# Schematic1.net
KiCad netlist of a schematic drawn in Altium Designer
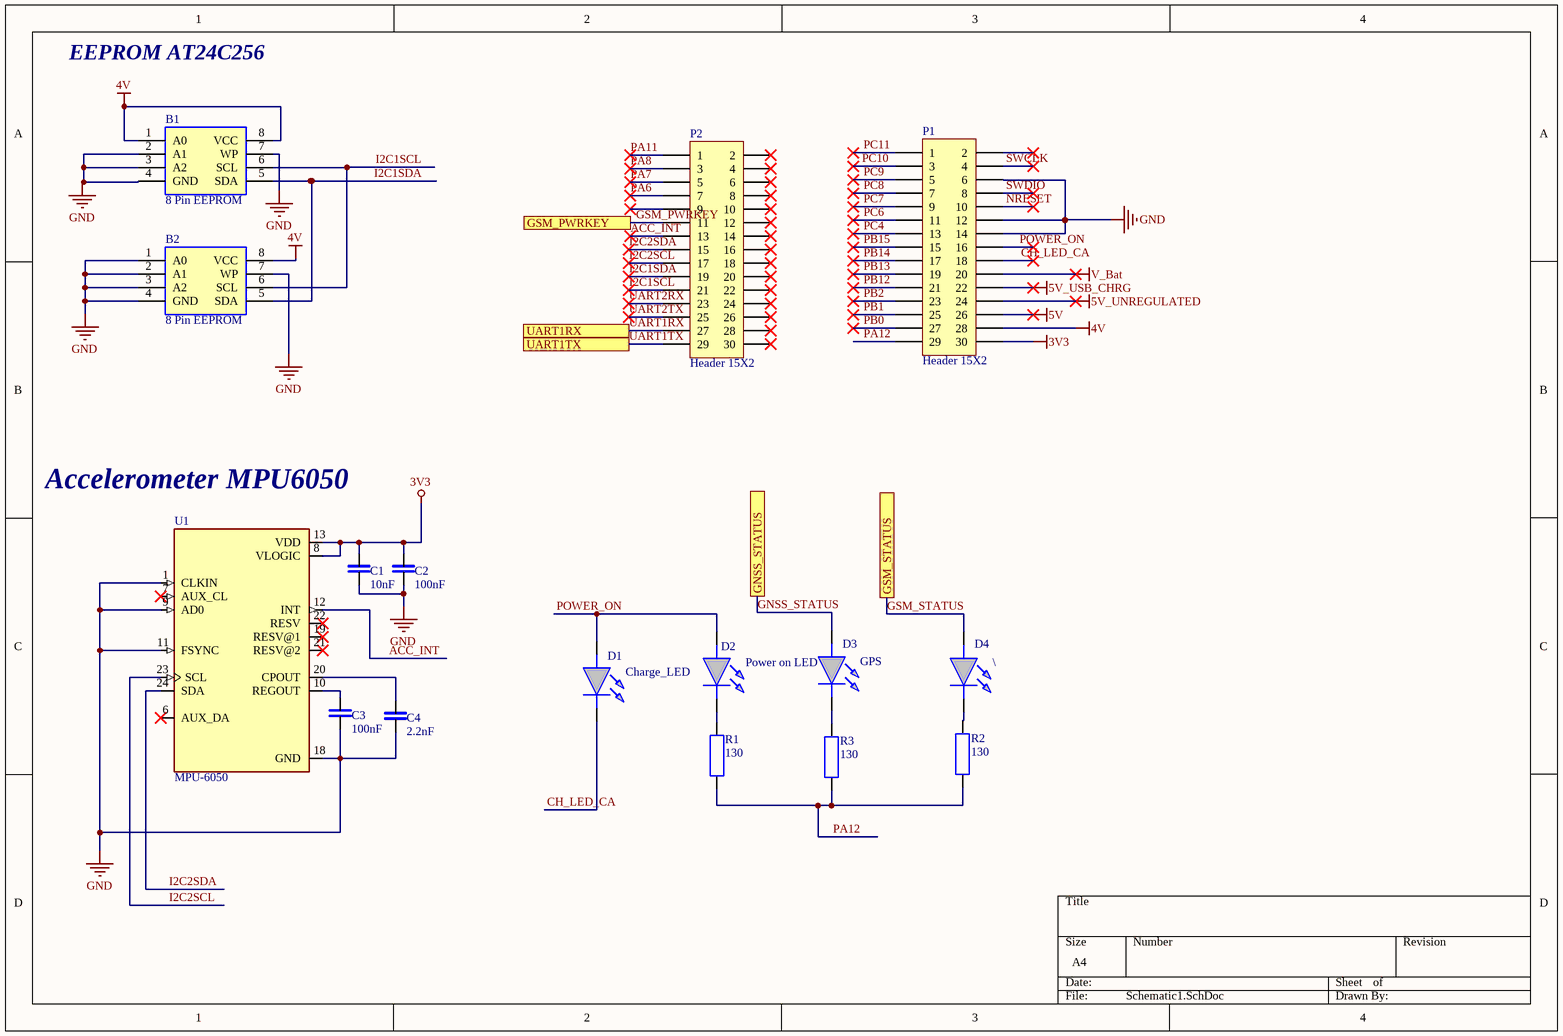
[diagram p0: Schematic1.SchDoc]

(export (version "E")
  (design (tool "Eeschema 10.0.6"))
  (components
    (comp (ref "B1")
      (value "8 Pin EEPROM")
      (footprint "AT24C256")
      (fields
        (field (name "MANUFACTURER_PART_NUMBER") "AT24C256C-SSHL-T")
        (field (name "MOUSER PART NUMBER") "556-AT24C256C-SSHL-T")
      )
      (libsource (lib "IC") (part "AT24C256C"))
    )
    (comp (ref "B2")
      (value "8 Pin EEPROM")
      (footprint "AT24C256")
      (fields
        (field (name "MANUFACTURER_PART_NUMBER") "AT24C256C-SSHL-T")
        (field (name "MOUSER PART NUMBER") "556-AT24C256C-SSHL-T")
      )
      (libsource (lib "IC") (part "AT24C256C"))
    )
    (comp (ref "C1")
      (value "10nF")
      (footprint "CAP_0805")
      (fields (field (name "MP") "LD051A270KAB2A"))
      (libsource (lib "Passive_Components") (part "SMT_CAP"))
    )
    (comp (ref "C2")
      (value "100nF")
      (footprint "CAP_0805")
      (fields (field (name "MP") "LD051A270KAB2A"))
      (libsource (lib "Passive_Components") (part "SMT_CAP"))
    )
    (comp (ref "C3")
      (value "100nF")
      (footprint "CAP_0805")
      (fields (field (name "MP") "LD051A270KAB2A"))
      (libsource (lib "Passive_Components") (part "SMT_CAP"))
    )
    (comp (ref "C4")
      (value "2.2nF")
      (footprint "CAP_0805")
      (fields (field (name "MP") "LD051A270KAB2A"))
      (libsource (lib "Passive_Components") (part "SMT_CAP"))
    )
    (comp (ref "D1")
      (value "Charge_LED")
      (footprint "LED_0805")
      (fields
        (field (name "MANUFACTURER_PART_NUMBER") "HSMH-C170")
        (field (name "MOUSER PART NUMBER") "630-HSMH-C170")
      )
      (libsource (lib "Diodes") (part "LED"))
    )
    (comp (ref "D2")
      (value "Power on LED")
      (footprint "LED_0805")
      (fields
        (field (name "MANUFACTURER_PART_NUMBER") "HSMH-C170")
        (field (name "MOUSER PART NUMBER") "630-HSMH-C170")
      )
      (libsource (lib "Diodes") (part "LED"))
    )
    (comp (ref "D3")
      (value "GPS")
      (footprint "LED_0805")
      (fields
        (field (name "MANUFACTURER_PART_NUMBER") "HSMH-C170")
        (field (name "MOUSER PART NUMBER") "630-HSMH-C170")
      )
      (libsource (lib "Diodes") (part "LED"))
    )
    (comp (ref "D4")
      (value "\\")
      (footprint "LED_0805")
      (fields
        (field (name "MANUFACTURER_PART_NUMBER") "HSMH-C170")
        (field (name "MOUSER PART NUMBER") "630-HSMH-C170")
      )
      (libsource (lib "Diodes") (part "LED"))
    )
    (comp (ref "P1")
      (value "Header 15X2")
      (footprint "HDR2X15")
      (description "Header, 15-Pin, Dual row")
      (fields (field (name "PUBLISHER") "Altium Limited"))
      (libsource (lib "Miscellaneous Connectors") (part "Header 15X2"))
    )
    (comp (ref "P2")
      (value "Header 15X2")
      (footprint "HDR2X15")
      (description "Header, 15-Pin, Dual row")
      (fields (field (name "PUBLISHER") "Altium Limited"))
      (libsource (lib "Miscellaneous Connectors") (part "Header 15X2"))
    )
    (comp (ref "R1")
      (value "130")
      (footprint "RES_0805")
      (fields
        (field (name "MP") "2-2176053-0")
        (field (name "TOLERANCE") "1%")
        (field (name "MF") "TE Connectivity")
      )
      (libsource (lib "Passive_Components") (part "SMT_RES"))
    )
    (comp (ref "R2")
      (value "130")
      (footprint "RES_0805")
      (fields
        (field (name "MP") "2-2176053-0")
        (field (name "TOLERANCE") "1%")
        (field (name "MF") "TE Connectivity")
      )
      (libsource (lib "Passive_Components") (part "SMT_RES"))
    )
    (comp (ref "R3")
      (value "130")
      (footprint "RES_0805")
      (fields
        (field (name "MP") "2-2176053-0")
        (field (name "TOLERANCE") "1%")
        (field (name "MF") "TE Connectivity")
      )
      (libsource (lib "Passive_Components") (part "SMT_RES"))
    )
    (comp (ref "U1")
      (value "MPU-6050")
      (footprint "MPU_6050")
      (fields (field (name "MF") "TDK InvenSense"))
      (libsource (lib "IC") (part "MPU-6050"))
    )
  )
  (nets
    (net (code "2") (name "/ACC_INT") (class "Default")
      (node (ref "P2") (pin "13") (pinfunction "13_13") (pintype "passive"))
      (node (ref "U1") (pin "12") (pinfunction "INT_12") (pintype "output"))
    )
    (net (code "3") (name "/CH_LED_CA") (class "Default")
      (node (ref "D1") (pin "1") (pinfunction "K_1") (pintype "passive"))
      (node (ref "P1") (pin "18") (pinfunction "18_18") (pintype "passive"))
    )
    (net (code "4") (name "/GNSS_STATUS") (class "Default")
      (node (ref "D3") (pin "2") (pinfunction "A_2") (pintype "passive"))
    )
    (net (code "5") (name "/GSM_PWRKEY") (class "Default")
      (node (ref "P2") (pin "11") (pinfunction "11_11") (pintype "passive"))
    )
    (net (code "6") (name "/GSM_STATUS") (class "Default")
      (node (ref "D4") (pin "2") (pinfunction "A_2") (pintype "passive"))
    )
    (net (code "7") (name "/I2C1SCL") (class "Default")
      (node (ref "B1") (pin "6") (pinfunction "SCL_6") (pintype "passive"))
      (node (ref "B2") (pin "6") (pinfunction "SCL_6") (pintype "passive"))
      (node (ref "P2") (pin "21") (pinfunction "21_21") (pintype "passive"))
    )
    (net (code "8") (name "/I2C1SDA") (class "Default")
      (node (ref "B1") (pin "5") (pinfunction "SDA_5") (pintype "passive"))
      (node (ref "B2") (pin "5") (pinfunction "SDA_5") (pintype "passive"))
      (node (ref "P2") (pin "19") (pinfunction "19_19") (pintype "passive"))
    )
    (net (code "9") (name "/I2C2SCL") (class "Default")
      (node (ref "P2") (pin "17") (pinfunction "17_17") (pintype "passive"))
      (node (ref "U1") (pin "23") (pinfunction "SCL_23") (pintype "input"))
    )
    (net (code "10") (name "/I2C2SDA") (class "Default")
      (node (ref "P2") (pin "15") (pinfunction "15_15") (pintype "passive"))
      (node (ref "U1") (pin "24") (pinfunction "SDA_24") (pintype "bidirectional"))
    )
    (net (code "11") (name "/NRESET") (class "Default")
      (node (ref "P1") (pin "10") (pinfunction "10_10") (pintype "passive+no_connect"))
    )
    (net (code "12") (name "/PA6") (class "Default")
      (node (ref "P2") (pin "7") (pinfunction "7_7") (pintype "passive+no_connect"))
    )
    (net (code "13") (name "/PA7") (class "Default")
      (node (ref "P2") (pin "5") (pinfunction "5_5") (pintype "passive+no_connect"))
    )
    (net (code "14") (name "/PA8") (class "Default")
      (node (ref "P2") (pin "3") (pinfunction "3_3") (pintype "passive+no_connect"))
    )
    (net (code "15") (name "/PA11") (class "Default")
      (node (ref "P2") (pin "1") (pinfunction "1_1") (pintype "passive+no_connect"))
    )
    (net (code "16") (name "/PA12") (class "Default")
      (node (ref "P1") (pin "29") (pinfunction "29_29") (pintype "passive"))
      (node (ref "R1") (pin "1") (pinfunction "1_1") (pintype "passive"))
      (node (ref "R2") (pin "1") (pinfunction "1_1") (pintype "passive"))
      (node (ref "R3") (pin "1") (pinfunction "1_1") (pintype "passive"))
    )
    (net (code "17") (name "/PB0") (class "Default")
      (node (ref "P1") (pin "27") (pinfunction "27_27") (pintype "passive+no_connect"))
    )
    (net (code "18") (name "/PB1") (class "Default")
      (node (ref "P1") (pin "25") (pinfunction "25_25") (pintype "passive+no_connect"))
    )
    (net (code "19") (name "/PB2") (class "Default")
      (node (ref "P1") (pin "23") (pinfunction "23_23") (pintype "passive+no_connect"))
    )
    (net (code "20") (name "/PB12") (class "Default")
      (node (ref "P1") (pin "21") (pinfunction "21_21") (pintype "passive+no_connect"))
    )
    (net (code "21") (name "/PB13") (class "Default")
      (node (ref "P1") (pin "19") (pinfunction "19_19") (pintype "passive+no_connect"))
    )
    (net (code "22") (name "/PB14") (class "Default")
      (node (ref "P1") (pin "17") (pinfunction "17_17") (pintype "passive+no_connect"))
    )
    (net (code "23") (name "/PB15") (class "Default")
      (node (ref "P1") (pin "15") (pinfunction "15_15") (pintype "passive+no_connect"))
    )
    (net (code "24") (name "/PC4") (class "Default")
      (node (ref "P1") (pin "13") (pinfunction "13_13") (pintype "passive+no_connect"))
    )
    (net (code "25") (name "/PC6") (class "Default")
      (node (ref "P1") (pin "11") (pinfunction "11_11") (pintype "passive+no_connect"))
    )
    (net (code "26") (name "/PC7") (class "Default")
      (node (ref "P1") (pin "9") (pinfunction "9_9") (pintype "passive+no_connect"))
    )
    (net (code "27") (name "/PC8") (class "Default")
      (node (ref "P1") (pin "7") (pinfunction "7_7") (pintype "passive+no_connect"))
    )
    (net (code "28") (name "/PC9") (class "Default")
      (node (ref "P1") (pin "5") (pinfunction "5_5") (pintype "passive+no_connect"))
    )
    (net (code "29") (name "/PC10") (class "Default")
      (node (ref "P1") (pin "3") (pinfunction "3_3") (pintype "passive+no_connect"))
    )
    (net (code "30") (name "/PC11") (class "Default")
      (node (ref "P1") (pin "1") (pinfunction "1_1") (pintype "passive+no_connect"))
    )
    (net (code "31") (name "/POWER_ON") (class "Default")
      (node (ref "D1") (pin "2") (pinfunction "A_2") (pintype "passive"))
      (node (ref "D2") (pin "2") (pinfunction "A_2") (pintype "passive"))
      (node (ref "P1") (pin "16") (pinfunction "16_16") (pintype "passive"))
    )
    (net (code "32") (name "/SWCLK") (class "Default")
      (node (ref "P1") (pin "4") (pinfunction "4_4") (pintype "passive+no_connect"))
    )
    (net (code "33") (name "/SWDIO") (class "Default")
      (node (ref "P1") (pin "8") (pinfunction "8_8") (pintype "passive+no_connect"))
    )
    (net (code "34") (name "/UART1RX") (class "Default")
      (node (ref "P2") (pin "27") (pinfunction "27_27") (pintype "passive"))
    )
    (net (code "35") (name "/UART1TX") (class "Default")
      (node (ref "P2") (pin "29") (pinfunction "29_29") (pintype "passive"))
    )
    (net (code "36") (name "/UART2RX") (class "Default")
      (node (ref "P2") (pin "23") (pinfunction "23_23") (pintype "passive+no_connect"))
    )
    (net (code "37") (name "/UART2TX") (class "Default")
      (node (ref "P2") (pin "25") (pinfunction "25_25") (pintype "passive+no_connect"))
    )
    (net (code "38") (name "3V3") (class "Default")
      (node (ref "C1") (pin "2") (pinfunction "2_2") (pintype "passive"))
      (node (ref "C2") (pin "2") (pinfunction "2_2") (pintype "passive"))
      (node (ref "P1") (pin "30") (pinfunction "30_30") (pintype "passive"))
      (node (ref "U1") (pin "13") (pinfunction "VDD_13") (pintype "power_in"))
      (node (ref "U1") (pin "8") (pinfunction "VLOGIC_8") (pintype "power_in"))
    )
    (net (code "39") (name "4V") (class "Default")
      (node (ref "B1") (pin "1") (pinfunction "A0_1") (pintype "passive"))
      (node (ref "B1") (pin "8") (pinfunction "VCC_8") (pintype "passive"))
      (node (ref "B2") (pin "8") (pinfunction "VCC_8") (pintype "passive"))
      (node (ref "P1") (pin "28") (pinfunction "28_28") (pintype "passive"))
    )
    (net (code "40") (name "5V") (class "Default")
      (node (ref "P1") (pin "26") (pinfunction "26_26") (pintype "passive"))
    )
    (net (code "41") (name "5V_UNREGULATED") (class "Default")
      (node (ref "P1") (pin "24") (pinfunction "24_24") (pintype "passive"))
    )
    (net (code "42") (name "5V_USB_CHRG") (class "Default")
      (node (ref "P1") (pin "22") (pinfunction "22_22") (pintype "passive"))
    )
    (net (code "43") (name "GND") (class "Default")
      (node (ref "B1") (pin "2") (pinfunction "A1_2") (pintype "passive"))
      (node (ref "B1") (pin "3") (pinfunction "A2_3") (pintype "passive"))
      (node (ref "B1") (pin "4") (pinfunction "GND_4") (pintype "passive"))
      (node (ref "B1") (pin "7") (pinfunction "WP_7") (pintype "passive"))
      (node (ref "B2") (pin "1") (pinfunction "A0_1") (pintype "passive"))
      (node (ref "B2") (pin "2") (pinfunction "A1_2") (pintype "passive"))
      (node (ref "B2") (pin "3") (pinfunction "A2_3") (pintype "passive"))
      (node (ref "B2") (pin "4") (pinfunction "GND_4") (pintype "passive"))
      (node (ref "B2") (pin "7") (pinfunction "WP_7") (pintype "passive"))
      (node (ref "C1") (pin "1") (pinfunction "1_1") (pintype "passive"))
      (node (ref "C2") (pin "1") (pinfunction "1_1") (pintype "passive"))
      (node (ref "C3") (pin "1") (pinfunction "1_1") (pintype "passive"))
      (node (ref "C4") (pin "1") (pinfunction "1_1") (pintype "passive"))
      (node (ref "P1") (pin "12") (pinfunction "12_12") (pintype "passive"))
      (node (ref "P1") (pin "14") (pinfunction "14_14") (pintype "passive"))
      (node (ref "P1") (pin "6") (pinfunction "6_6") (pintype "passive"))
      (node (ref "U1") (pin "1") (pinfunction "CLKIN_1") (pintype "input"))
      (node (ref "U1") (pin "11") (pinfunction "FSYNC_11") (pintype "input"))
      (node (ref "U1") (pin "18") (pinfunction "GND_18") (pintype "power_in"))
      (node (ref "U1") (pin "9") (pinfunction "AD0_9") (pintype "input"))
    )
    (net (code "44") (name "Net-(D2-K)") (class "Default")
      (node (ref "D2") (pin "1") (pinfunction "K_1") (pintype "passive"))
      (node (ref "R1") (pin "2") (pinfunction "2_2") (pintype "passive"))
    )
    (net (code "45") (name "Net-(D3-K)") (class "Default")
      (node (ref "D3") (pin "1") (pinfunction "K_1") (pintype "passive"))
      (node (ref "R3") (pin "2") (pinfunction "2_2") (pintype "passive"))
    )
    (net (code "46") (name "Net-(D4-K)") (class "Default")
      (node (ref "D4") (pin "1") (pinfunction "K_1") (pintype "passive"))
      (node (ref "R2") (pin "2") (pinfunction "2_2") (pintype "passive"))
    )
    (net (code "47") (name "Net-(U1-CPOUT)") (class "Default")
      (node (ref "C4") (pin "2") (pinfunction "2_2") (pintype "passive"))
      (node (ref "U1") (pin "20") (pinfunction "CPOUT_20") (pintype "passive"))
    )
    (net (code "48") (name "Net-(U1-REGOUT)") (class "Default")
      (node (ref "C3") (pin "2") (pinfunction "2_2") (pintype "passive"))
      (node (ref "U1") (pin "10") (pinfunction "REGOUT_10") (pintype "passive"))
    )
    (net (code "49") (name "V_Bat") (class "Default")
      (node (ref "P1") (pin "20") (pinfunction "20_20") (pintype "passive"))
    )
    (net (code "50") (name "unconnected-(P1-Pad2)") (class "Default")
      (node (ref "P1") (pin "2") (pinfunction "2_2") (pintype "passive+no_connect"))
    )
    (net (code "51") (name "unconnected-(P2-Pad2)") (class "Default")
      (node (ref "P2") (pin "2") (pinfunction "2_2") (pintype "passive+no_connect"))
    )
    (net (code "52") (name "unconnected-(P2-Pad4)") (class "Default")
      (node (ref "P2") (pin "4") (pinfunction "4_4") (pintype "passive+no_connect"))
    )
    (net (code "53") (name "unconnected-(P2-Pad6)") (class "Default")
      (node (ref "P2") (pin "6") (pinfunction "6_6") (pintype "passive+no_connect"))
    )
    (net (code "54") (name "unconnected-(P2-Pad8)") (class "Default")
      (node (ref "P2") (pin "8") (pinfunction "8_8") (pintype "passive+no_connect"))
    )
    (net (code "55") (name "unconnected-(P2-Pad9)") (class "Default")
      (node (ref "P2") (pin "9") (pinfunction "9_9") (pintype "passive+no_connect"))
    )
    (net (code "56") (name "unconnected-(P2-Pad10)") (class "Default")
      (node (ref "P2") (pin "10") (pinfunction "10_10") (pintype "passive+no_connect"))
    )
    (net (code "57") (name "unconnected-(P2-Pad12)") (class "Default")
      (node (ref "P2") (pin "12") (pinfunction "12_12") (pintype "passive+no_connect"))
    )
    (net (code "58") (name "unconnected-(P2-Pad14)") (class "Default")
      (node (ref "P2") (pin "14") (pinfunction "14_14") (pintype "passive+no_connect"))
    )
    (net (code "59") (name "unconnected-(P2-Pad16)") (class "Default")
      (node (ref "P2") (pin "16") (pinfunction "16_16") (pintype "passive+no_connect"))
    )
    (net (code "60") (name "unconnected-(P2-Pad18)") (class "Default")
      (node (ref "P2") (pin "18") (pinfunction "18_18") (pintype "passive+no_connect"))
    )
    (net (code "61") (name "unconnected-(P2-Pad20)") (class "Default")
      (node (ref "P2") (pin "20") (pinfunction "20_20") (pintype "passive+no_connect"))
    )
    (net (code "62") (name "unconnected-(P2-Pad22)") (class "Default")
      (node (ref "P2") (pin "22") (pinfunction "22_22") (pintype "passive+no_connect"))
    )
    (net (code "63") (name "unconnected-(P2-Pad24)") (class "Default")
      (node (ref "P2") (pin "24") (pinfunction "24_24") (pintype "passive+no_connect"))
    )
    (net (code "64") (name "unconnected-(P2-Pad26)") (class "Default")
      (node (ref "P2") (pin "26") (pinfunction "26_26") (pintype "passive+no_connect"))
    )
    (net (code "65") (name "unconnected-(P2-Pad28)") (class "Default")
      (node (ref "P2") (pin "28") (pinfunction "28_28") (pintype "passive+no_connect"))
    )
    (net (code "66") (name "unconnected-(P2-Pad30)") (class "Default")
      (node (ref "P2") (pin "30") (pinfunction "30_30") (pintype "passive+no_connect"))
    )
    (net (code "67") (name "unconnected-(U1-AUX_CL-Pad7)") (class "Default")
      (node (ref "U1") (pin "7") (pinfunction "AUX_CL_7") (pintype "input+no_connect"))
    )
    (net (code "68") (name "unconnected-(U1-AUX_DA-Pad6)") (class "Default")
      (node (ref "U1") (pin "6") (pinfunction "AUX_DA_6") (pintype "bidirectional+no_connect"))
    )
    (net (code "69") (name "unconnected-(U1-RESV-Pad22)") (class "Default")
      (node (ref "U1") (pin "22") (pinfunction "RESV_22") (pintype "passive+no_connect"))
    )
    (net (code "70") (name "unconnected-(U1-RESV@1-Pad19)") (class "Default")
      (node (ref "U1") (pin "19") (pinfunction "RESV@1_19") (pintype "passive+no_connect"))
    )
    (net (code "71") (name "unconnected-(U1-RESV@2-Pad21)") (class "Default")
      (node (ref "U1") (pin "21") (pinfunction "RESV@2_21") (pintype "passive+no_connect"))
    )
  )
)
